# 1_routed_1register.net
KiCad netlist of a schematic drawn in EAGLE
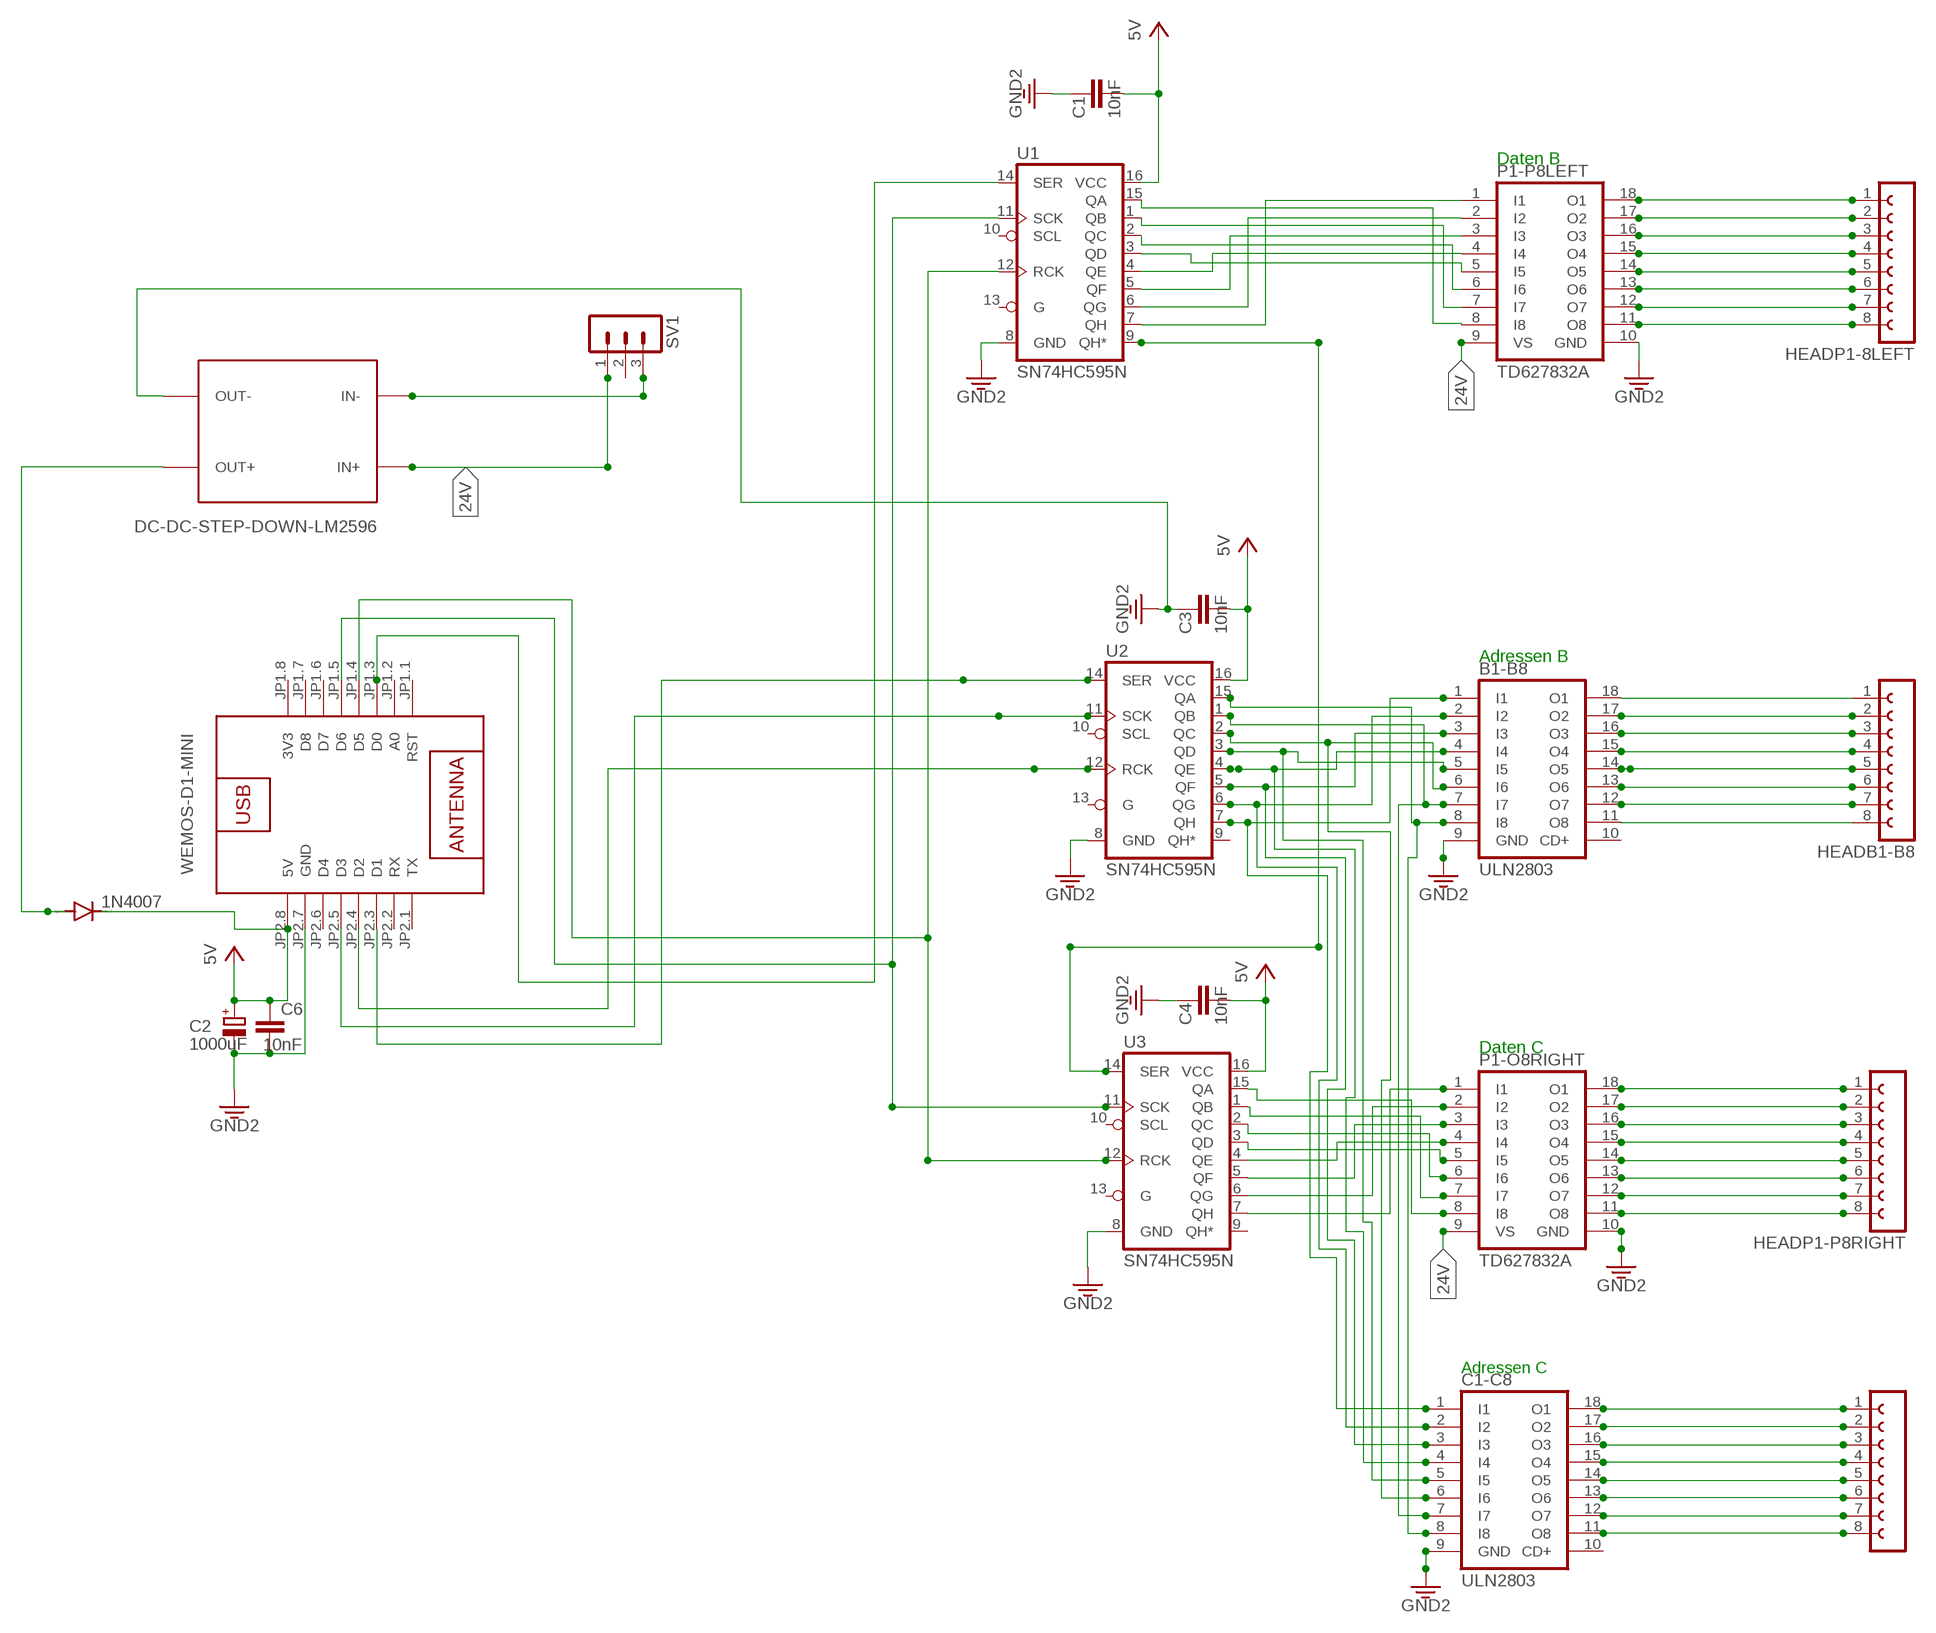
[diagram p0: schematic, sheet 1]

(export (version "E")
  (design (tool "Eeschema 10.0.6"))
  (components
    (comp (ref "1N4007")
      (value "DIODE-D-2.5")
      (footprint "eagle-import:D-2.5")
      (libsource (lib "eagle-import") (part "DIODE-D-2.5"))
    )
    (comp (ref "B1-B8")
      (value "ULN2803")
      (footprint "eagle-import:DIL18")
      (libsource (lib "eagle-import") (part "ULN2803A"))
    )
    (comp (ref "C1")
      (value "10nF")
      (footprint "eagle-import:C025-025X050")
      (libsource (lib "eagle-import") (part "C-EU025-025X050"))
    )
    (comp (ref "C1-C8")
      (value "ULN2803")
      (footprint "eagle-import:DIL18")
      (libsource (lib "eagle-import") (part "ULN2803A"))
    )
    (comp (ref "C2")
      (value "1000uF")
      (footprint "eagle-import:E5-10,5")
      (libsource (lib "eagle-import") (part "CPOL-EUE5-10.5"))
    )
    (comp (ref "C3")
      (value "10nF")
      (footprint "eagle-import:C025-025X050")
      (libsource (lib "eagle-import") (part "C-EU025-025X050"))
    )
    (comp (ref "C4")
      (value "10nF")
      (footprint "eagle-import:C025-025X050")
      (libsource (lib "eagle-import") (part "C-EU025-025X050"))
    )
    (comp (ref "C6")
      (value "10nF")
      (footprint "eagle-import:C025-025X050")
      (libsource (lib "eagle-import") (part "C-EU025-025X050"))
    )
    (comp (ref "HEADB1-B8")
      (value "FE08-1")
      (footprint "eagle-import:FE08")
      (libsource (lib "eagle-import") (part "FE08-1"))
    )
    (comp (ref "HEADC1-C8")
      (value "FE08-1")
      (footprint "eagle-import:FE08")
      (libsource (lib "eagle-import") (part "FE08-1"))
    )
    (comp (ref "HEADP1-8LEFT")
      (value "FE08-1")
      (footprint "eagle-import:FE08")
      (libsource (lib "eagle-import") (part "FE08-1"))
    )
    (comp (ref "HEADP1-P8RIGHT")
      (value "FE08-1")
      (footprint "eagle-import:FE08")
      (libsource (lib "eagle-import") (part "FE08-1"))
    )
    (comp (ref "P1-O8RIGHT")
      (value "TD627832A")
      (footprint "eagle-import:DIL18")
      (libsource (lib "eagle-import") (part "TD62783A2"))
    )
    (comp (ref "P1-P8LEFT")
      (value "TD627832A")
      (footprint "eagle-import:DIL18")
      (libsource (lib "eagle-import") (part "TD62783A2"))
    )
    (comp (ref "SV1")
      (value "MA03-1")
      (footprint "eagle-import:MA03-1")
      (libsource (lib "eagle-import") (part "MA03-1"))
    )
    (comp (ref "U$1")
      (value "WEMOS-D1-MINI")
      (footprint "eagle-import:WEMOS-D1-MINI")
      (libsource (lib "eagle-import") (part "WEMOS-D1-MINI"))
    )
    (comp (ref "U$2")
      (value "DC-DC-STEP-DOWN-LM2596")
      (footprint "eagle-import:DC-DC-STEP-DOWN-LM2596")
      (libsource (lib "eagle-import") (part "DC-DC-STEP-DOWN-LM2596"))
    )
    (comp (ref "U1")
      (value "SN74HC595N")
      (footprint "eagle-import:DIP16")
      (libsource (lib "eagle-import") (part "74595NHC"))
    )
    (comp (ref "U2")
      (value "SN74HC595N")
      (footprint "eagle-import:DIP16")
      (libsource (lib "eagle-import") (part "74595NHC"))
    )
    (comp (ref "U3")
      (value "SN74HC595N")
      (footprint "eagle-import:DIP16")
      (libsource (lib "eagle-import") (part "74595NHC"))
    )
  )
  (nets
    (net (code "1") (name "/3V3") (class "Default")
      (node (ref "U$1") (pin "JP1.8") (pinfunction "3V3_JP1.8") (pintype "power_in"))
    )
    (net (code "2") (name "5V") (class "Default")
      (node (ref "1N4007") (pin "C") (pinfunction "C_C") (pintype "passive"))
      (node (ref "C1") (pin "2") (pinfunction "2_2") (pintype "passive"))
      (node (ref "C2") (pin "+") (pinfunction "+_+") (pintype "passive"))
      (node (ref "C3") (pin "2") (pinfunction "2_2") (pintype "passive"))
      (node (ref "C4") (pin "2") (pinfunction "2_2") (pintype "passive"))
      (node (ref "C6") (pin "1") (pinfunction "1_1") (pintype "passive"))
      (node (ref "U$1") (pin "JP2.8") (pinfunction "5V_JP2.8") (pintype "power_in"))
      (node (ref "U1") (pin "16") (pinfunction "VCC_16") (pintype "power_in"))
      (node (ref "U2") (pin "16") (pinfunction "VCC_16") (pintype "power_in"))
      (node (ref "U3") (pin "16") (pinfunction "VCC_16") (pintype "power_in"))
    )
    (net (code "3") (name "24V") (class "Default")
      (node (ref "P1-O8RIGHT") (pin "9") (pinfunction "VS_9") (pintype "passive"))
      (node (ref "P1-P8LEFT") (pin "9") (pinfunction "VS_9") (pintype "passive"))
      (node (ref "SV1") (pin "1") (pinfunction "1_1") (pintype "passive"))
      (node (ref "U$2") (pin "IN+") (pinfunction "IN+_IN+") (pintype "bidirectional"))
    )
    (net (code "4") (name "GND2") (class "Default")
      (node (ref "B1-B8") (pin "9") (pinfunction "GND_9") (pintype "power_in"))
      (node (ref "C1") (pin "1") (pinfunction "1_1") (pintype "passive"))
      (node (ref "C1-C8") (pin "9") (pinfunction "GND_9") (pintype "power_in"))
      (node (ref "C2") (pin "-") (pinfunction "-_-") (pintype "passive"))
      (node (ref "C3") (pin "1") (pinfunction "1_1") (pintype "passive"))
      (node (ref "C4") (pin "1") (pinfunction "1_1") (pintype "passive"))
      (node (ref "C6") (pin "2") (pinfunction "2_2") (pintype "passive"))
      (node (ref "P1-O8RIGHT") (pin "10") (pinfunction "GND_10") (pintype "power_in"))
      (node (ref "P1-P8LEFT") (pin "10") (pinfunction "GND_10") (pintype "power_in"))
      (node (ref "U$1") (pin "JP2.7") (pinfunction "GND_JP2.7") (pintype "power_in"))
      (node (ref "U$2") (pin "OUT-") (pinfunction "OUT-_OUT-") (pintype "bidirectional"))
      (node (ref "U1") (pin "8") (pinfunction "GND_8") (pintype "power_in"))
      (node (ref "U2") (pin "8") (pinfunction "GND_8") (pintype "power_in"))
      (node (ref "U3") (pin "8") (pinfunction "GND_8") (pintype "power_in"))
    )
    (net (code "5") (name "Net-(1N4007-PadA)") (class "Default")
      (node (ref "1N4007") (pin "A") (pinfunction "A_A") (pintype "passive"))
      (node (ref "U$2") (pin "OUT+") (pinfunction "OUT+_OUT+") (pintype "bidirectional"))
    )
    (net (code "6") (name "Net-(B1-B8-I1)") (class "Default")
      (node (ref "B1-B8") (pin "1") (pinfunction "I1_1") (pintype "input"))
      (node (ref "C1-C8") (pin "1") (pinfunction "I1_1") (pintype "input"))
      (node (ref "U2") (pin "7") (pinfunction "QH_7") (pintype "tri_state"))
    )
    (net (code "7") (name "Net-(B1-B8-I2)") (class "Default")
      (node (ref "B1-B8") (pin "2") (pinfunction "I2_2") (pintype "input"))
      (node (ref "C1-C8") (pin "2") (pinfunction "I2_2") (pintype "input"))
      (node (ref "U2") (pin "6") (pinfunction "QG_6") (pintype "tri_state"))
    )
    (net (code "8") (name "Net-(B1-B8-I3)") (class "Default")
      (node (ref "B1-B8") (pin "3") (pinfunction "I3_3") (pintype "input"))
      (node (ref "C1-C8") (pin "3") (pinfunction "I3_3") (pintype "input"))
      (node (ref "U2") (pin "5") (pinfunction "QF_5") (pintype "tri_state"))
    )
    (net (code "9") (name "Net-(B1-B8-I4)") (class "Default")
      (node (ref "B1-B8") (pin "4") (pinfunction "I4_4") (pintype "input"))
      (node (ref "C1-C8") (pin "4") (pinfunction "I4_4") (pintype "input"))
      (node (ref "U2") (pin "4") (pinfunction "QE_4") (pintype "tri_state"))
    )
    (net (code "10") (name "Net-(B1-B8-I5)") (class "Default")
      (node (ref "B1-B8") (pin "5") (pinfunction "I5_5") (pintype "input"))
      (node (ref "C1-C8") (pin "5") (pinfunction "I5_5") (pintype "input"))
      (node (ref "U2") (pin "3") (pinfunction "QD_3") (pintype "tri_state"))
    )
    (net (code "11") (name "Net-(B1-B8-I6)") (class "Default")
      (node (ref "B1-B8") (pin "6") (pinfunction "I6_6") (pintype "input"))
      (node (ref "C1-C8") (pin "6") (pinfunction "I6_6") (pintype "input"))
      (node (ref "U2") (pin "2") (pinfunction "QC_2") (pintype "tri_state"))
    )
    (net (code "12") (name "Net-(B1-B8-I7)") (class "Default")
      (node (ref "B1-B8") (pin "7") (pinfunction "I7_7") (pintype "input"))
      (node (ref "C1-C8") (pin "7") (pinfunction "I7_7") (pintype "input"))
      (node (ref "U2") (pin "1") (pinfunction "QB_1") (pintype "tri_state"))
    )
    (net (code "13") (name "Net-(B1-B8-I8)") (class "Default")
      (node (ref "B1-B8") (pin "8") (pinfunction "I8_8") (pintype "input"))
      (node (ref "C1-C8") (pin "8") (pinfunction "I8_8") (pintype "input"))
      (node (ref "U2") (pin "15") (pinfunction "QA_15") (pintype "tri_state"))
    )
    (net (code "14") (name "Net-(B1-B8-O1)") (class "Default")
      (node (ref "B1-B8") (pin "18") (pinfunction "O1_18") (pintype "open_collector"))
      (node (ref "HEADB1-B8") (pin "1") (pinfunction "1_1") (pintype "passive"))
    )
    (net (code "15") (name "Net-(B1-B8-O2)") (class "Default")
      (node (ref "B1-B8") (pin "17") (pinfunction "O2_17") (pintype "open_collector"))
      (node (ref "HEADB1-B8") (pin "2") (pinfunction "2_2") (pintype "passive"))
    )
    (net (code "16") (name "Net-(B1-B8-O3)") (class "Default")
      (node (ref "B1-B8") (pin "16") (pinfunction "O3_16") (pintype "open_collector"))
      (node (ref "HEADB1-B8") (pin "3") (pinfunction "3_3") (pintype "passive"))
    )
    (net (code "17") (name "Net-(B1-B8-O4)") (class "Default")
      (node (ref "B1-B8") (pin "15") (pinfunction "O4_15") (pintype "open_collector"))
      (node (ref "HEADB1-B8") (pin "4") (pinfunction "4_4") (pintype "passive"))
    )
    (net (code "18") (name "Net-(B1-B8-O5)") (class "Default")
      (node (ref "B1-B8") (pin "14") (pinfunction "O5_14") (pintype "open_collector"))
      (node (ref "HEADB1-B8") (pin "5") (pinfunction "5_5") (pintype "passive"))
    )
    (net (code "19") (name "Net-(B1-B8-O6)") (class "Default")
      (node (ref "B1-B8") (pin "13") (pinfunction "O6_13") (pintype "open_collector"))
      (node (ref "HEADB1-B8") (pin "6") (pinfunction "6_6") (pintype "passive"))
    )
    (net (code "20") (name "Net-(B1-B8-O7)") (class "Default")
      (node (ref "B1-B8") (pin "12") (pinfunction "O7_12") (pintype "open_collector"))
      (node (ref "HEADB1-B8") (pin "7") (pinfunction "7_7") (pintype "passive"))
    )
    (net (code "21") (name "Net-(B1-B8-O8)") (class "Default")
      (node (ref "B1-B8") (pin "11") (pinfunction "O8_11") (pintype "open_collector"))
      (node (ref "HEADB1-B8") (pin "8") (pinfunction "8_8") (pintype "passive"))
    )
    (net (code "22") (name "Net-(C1-C8-O1)") (class "Default")
      (node (ref "C1-C8") (pin "18") (pinfunction "O1_18") (pintype "open_collector"))
      (node (ref "HEADC1-C8") (pin "1") (pinfunction "1_1") (pintype "passive"))
    )
    (net (code "23") (name "Net-(C1-C8-O2)") (class "Default")
      (node (ref "C1-C8") (pin "17") (pinfunction "O2_17") (pintype "open_collector"))
      (node (ref "HEADC1-C8") (pin "2") (pinfunction "2_2") (pintype "passive"))
    )
    (net (code "24") (name "Net-(C1-C8-O3)") (class "Default")
      (node (ref "C1-C8") (pin "16") (pinfunction "O3_16") (pintype "open_collector"))
      (node (ref "HEADC1-C8") (pin "3") (pinfunction "3_3") (pintype "passive"))
    )
    (net (code "25") (name "Net-(C1-C8-O4)") (class "Default")
      (node (ref "C1-C8") (pin "15") (pinfunction "O4_15") (pintype "open_collector"))
      (node (ref "HEADC1-C8") (pin "4") (pinfunction "4_4") (pintype "passive"))
    )
    (net (code "26") (name "Net-(C1-C8-O5)") (class "Default")
      (node (ref "C1-C8") (pin "14") (pinfunction "O5_14") (pintype "open_collector"))
      (node (ref "HEADC1-C8") (pin "5") (pinfunction "5_5") (pintype "passive"))
    )
    (net (code "27") (name "Net-(C1-C8-O6)") (class "Default")
      (node (ref "C1-C8") (pin "13") (pinfunction "O6_13") (pintype "open_collector"))
      (node (ref "HEADC1-C8") (pin "6") (pinfunction "6_6") (pintype "passive"))
    )
    (net (code "28") (name "Net-(C1-C8-O7)") (class "Default")
      (node (ref "C1-C8") (pin "12") (pinfunction "O7_12") (pintype "open_collector"))
      (node (ref "HEADC1-C8") (pin "7") (pinfunction "7_7") (pintype "passive"))
    )
    (net (code "29") (name "Net-(C1-C8-O8)") (class "Default")
      (node (ref "C1-C8") (pin "11") (pinfunction "O8_11") (pintype "open_collector"))
      (node (ref "HEADC1-C8") (pin "8") (pinfunction "8_8") (pintype "passive"))
    )
    (net (code "30") (name "Net-(P1-O8RIGHT-I1)") (class "Default")
      (node (ref "P1-O8RIGHT") (pin "1") (pinfunction "I1_1") (pintype "input"))
      (node (ref "U3") (pin "7") (pinfunction "QH_7") (pintype "tri_state"))
    )
    (net (code "31") (name "Net-(P1-O8RIGHT-I2)") (class "Default")
      (node (ref "P1-O8RIGHT") (pin "2") (pinfunction "I2_2") (pintype "input"))
      (node (ref "U3") (pin "6") (pinfunction "QG_6") (pintype "tri_state"))
    )
    (net (code "32") (name "Net-(P1-O8RIGHT-I3)") (class "Default")
      (node (ref "P1-O8RIGHT") (pin "3") (pinfunction "I3_3") (pintype "input"))
      (node (ref "U3") (pin "5") (pinfunction "QF_5") (pintype "tri_state"))
    )
    (net (code "33") (name "Net-(P1-O8RIGHT-I4)") (class "Default")
      (node (ref "P1-O8RIGHT") (pin "4") (pinfunction "I4_4") (pintype "input"))
      (node (ref "U3") (pin "4") (pinfunction "QE_4") (pintype "tri_state"))
    )
    (net (code "34") (name "Net-(P1-O8RIGHT-I5)") (class "Default")
      (node (ref "P1-O8RIGHT") (pin "5") (pinfunction "I5_5") (pintype "input"))
      (node (ref "U3") (pin "3") (pinfunction "QD_3") (pintype "tri_state"))
    )
    (net (code "35") (name "Net-(P1-O8RIGHT-I6)") (class "Default")
      (node (ref "P1-O8RIGHT") (pin "6") (pinfunction "I6_6") (pintype "input"))
      (node (ref "U3") (pin "2") (pinfunction "QC_2") (pintype "tri_state"))
    )
    (net (code "36") (name "Net-(P1-O8RIGHT-I7)") (class "Default")
      (node (ref "P1-O8RIGHT") (pin "7") (pinfunction "I7_7") (pintype "input"))
      (node (ref "U3") (pin "1") (pinfunction "QB_1") (pintype "tri_state"))
    )
    (net (code "37") (name "Net-(P1-O8RIGHT-I8)") (class "Default")
      (node (ref "P1-O8RIGHT") (pin "8") (pinfunction "I8_8") (pintype "input"))
      (node (ref "U3") (pin "15") (pinfunction "QA_15") (pintype "tri_state"))
    )
    (net (code "38") (name "Net-(P1-O8RIGHT-O1)") (class "Default")
      (node (ref "HEADP1-P8RIGHT") (pin "1") (pinfunction "1_1") (pintype "passive"))
      (node (ref "P1-O8RIGHT") (pin "18") (pinfunction "O1_18") (pintype "open_collector"))
    )
    (net (code "39") (name "Net-(P1-O8RIGHT-O2)") (class "Default")
      (node (ref "HEADP1-P8RIGHT") (pin "2") (pinfunction "2_2") (pintype "passive"))
      (node (ref "P1-O8RIGHT") (pin "17") (pinfunction "O2_17") (pintype "open_collector"))
    )
    (net (code "40") (name "Net-(P1-O8RIGHT-O3)") (class "Default")
      (node (ref "HEADP1-P8RIGHT") (pin "3") (pinfunction "3_3") (pintype "passive"))
      (node (ref "P1-O8RIGHT") (pin "16") (pinfunction "O3_16") (pintype "open_collector"))
    )
    (net (code "41") (name "Net-(P1-O8RIGHT-O4)") (class "Default")
      (node (ref "HEADP1-P8RIGHT") (pin "4") (pinfunction "4_4") (pintype "passive"))
      (node (ref "P1-O8RIGHT") (pin "15") (pinfunction "O4_15") (pintype "open_collector"))
    )
    (net (code "42") (name "Net-(P1-O8RIGHT-O5)") (class "Default")
      (node (ref "HEADP1-P8RIGHT") (pin "5") (pinfunction "5_5") (pintype "passive"))
      (node (ref "P1-O8RIGHT") (pin "14") (pinfunction "O5_14") (pintype "open_collector"))
    )
    (net (code "43") (name "Net-(P1-O8RIGHT-O6)") (class "Default")
      (node (ref "HEADP1-P8RIGHT") (pin "6") (pinfunction "6_6") (pintype "passive"))
      (node (ref "P1-O8RIGHT") (pin "13") (pinfunction "O6_13") (pintype "open_collector"))
    )
    (net (code "44") (name "Net-(P1-O8RIGHT-O7)") (class "Default")
      (node (ref "HEADP1-P8RIGHT") (pin "7") (pinfunction "7_7") (pintype "passive"))
      (node (ref "P1-O8RIGHT") (pin "12") (pinfunction "O7_12") (pintype "open_collector"))
    )
    (net (code "45") (name "Net-(P1-O8RIGHT-O8)") (class "Default")
      (node (ref "HEADP1-P8RIGHT") (pin "8") (pinfunction "8_8") (pintype "passive"))
      (node (ref "P1-O8RIGHT") (pin "11") (pinfunction "O8_11") (pintype "open_collector"))
    )
    (net (code "46") (name "Net-(P1-P8LEFT-I1)") (class "Default")
      (node (ref "P1-P8LEFT") (pin "1") (pinfunction "I1_1") (pintype "input"))
      (node (ref "U1") (pin "7") (pinfunction "QH_7") (pintype "tri_state"))
    )
    (net (code "47") (name "Net-(P1-P8LEFT-I2)") (class "Default")
      (node (ref "P1-P8LEFT") (pin "2") (pinfunction "I2_2") (pintype "input"))
      (node (ref "U1") (pin "6") (pinfunction "QG_6") (pintype "tri_state"))
    )
    (net (code "48") (name "Net-(P1-P8LEFT-I3)") (class "Default")
      (node (ref "P1-P8LEFT") (pin "3") (pinfunction "I3_3") (pintype "input"))
      (node (ref "U1") (pin "5") (pinfunction "QF_5") (pintype "tri_state"))
    )
    (net (code "49") (name "Net-(P1-P8LEFT-I4)") (class "Default")
      (node (ref "P1-P8LEFT") (pin "4") (pinfunction "I4_4") (pintype "input"))
      (node (ref "U1") (pin "4") (pinfunction "QE_4") (pintype "tri_state"))
    )
    (net (code "50") (name "Net-(P1-P8LEFT-I5)") (class "Default")
      (node (ref "P1-P8LEFT") (pin "5") (pinfunction "I5_5") (pintype "input"))
      (node (ref "U1") (pin "3") (pinfunction "QD_3") (pintype "tri_state"))
    )
    (net (code "51") (name "Net-(P1-P8LEFT-I6)") (class "Default")
      (node (ref "P1-P8LEFT") (pin "6") (pinfunction "I6_6") (pintype "input"))
      (node (ref "U1") (pin "2") (pinfunction "QC_2") (pintype "tri_state"))
    )
    (net (code "52") (name "Net-(P1-P8LEFT-I7)") (class "Default")
      (node (ref "P1-P8LEFT") (pin "7") (pinfunction "I7_7") (pintype "input"))
      (node (ref "U1") (pin "1") (pinfunction "QB_1") (pintype "tri_state"))
    )
    (net (code "53") (name "Net-(P1-P8LEFT-I8)") (class "Default")
      (node (ref "P1-P8LEFT") (pin "8") (pinfunction "I8_8") (pintype "input"))
      (node (ref "U1") (pin "15") (pinfunction "QA_15") (pintype "tri_state"))
    )
    (net (code "54") (name "Net-(P1-P8LEFT-O1)") (class "Default")
      (node (ref "HEADP1-8LEFT") (pin "1") (pinfunction "1_1") (pintype "passive"))
      (node (ref "P1-P8LEFT") (pin "18") (pinfunction "O1_18") (pintype "open_collector"))
    )
    (net (code "55") (name "Net-(P1-P8LEFT-O2)") (class "Default")
      (node (ref "HEADP1-8LEFT") (pin "2") (pinfunction "2_2") (pintype "passive"))
      (node (ref "P1-P8LEFT") (pin "17") (pinfunction "O2_17") (pintype "open_collector"))
    )
    (net (code "56") (name "Net-(P1-P8LEFT-O3)") (class "Default")
      (node (ref "HEADP1-8LEFT") (pin "3") (pinfunction "3_3") (pintype "passive"))
      (node (ref "P1-P8LEFT") (pin "16") (pinfunction "O3_16") (pintype "open_collector"))
    )
    (net (code "57") (name "Net-(P1-P8LEFT-O4)") (class "Default")
      (node (ref "HEADP1-8LEFT") (pin "4") (pinfunction "4_4") (pintype "passive"))
      (node (ref "P1-P8LEFT") (pin "15") (pinfunction "O4_15") (pintype "open_collector"))
    )
    (net (code "58") (name "Net-(P1-P8LEFT-O5)") (class "Default")
      (node (ref "HEADP1-8LEFT") (pin "5") (pinfunction "5_5") (pintype "passive"))
      (node (ref "P1-P8LEFT") (pin "14") (pinfunction "O5_14") (pintype "open_collector"))
    )
    (net (code "59") (name "Net-(P1-P8LEFT-O6)") (class "Default")
      (node (ref "HEADP1-8LEFT") (pin "6") (pinfunction "6_6") (pintype "passive"))
      (node (ref "P1-P8LEFT") (pin "13") (pinfunction "O6_13") (pintype "open_collector"))
    )
    (net (code "60") (name "Net-(P1-P8LEFT-O7)") (class "Default")
      (node (ref "HEADP1-8LEFT") (pin "7") (pinfunction "7_7") (pintype "passive"))
      (node (ref "P1-P8LEFT") (pin "12") (pinfunction "O7_12") (pintype "open_collector"))
    )
    (net (code "61") (name "Net-(P1-P8LEFT-O8)") (class "Default")
      (node (ref "HEADP1-8LEFT") (pin "8") (pinfunction "8_8") (pintype "passive"))
      (node (ref "P1-P8LEFT") (pin "11") (pinfunction "O8_11") (pintype "open_collector"))
    )
    (net (code "62") (name "Net-(SV1-Pad3)") (class "Default")
      (node (ref "SV1") (pin "3") (pinfunction "3_3") (pintype "passive"))
      (node (ref "U$2") (pin "IN-") (pinfunction "IN-_IN-") (pintype "bidirectional"))
    )
    (net (code "63") (name "Net-(U$1-D0)") (class "Default")
      (node (ref "U$1") (pin "JP1.3") (pinfunction "D0_JP1.3") (pintype "bidirectional"))
      (node (ref "U1") (pin "14") (pinfunction "SER_14") (pintype "input"))
    )
    (net (code "64") (name "Net-(U$1-D1)") (class "Default")
      (node (ref "U$1") (pin "JP2.3") (pinfunction "D1_JP2.3") (pintype "bidirectional"))
      (node (ref "U2") (pin "14") (pinfunction "SER_14") (pintype "input"))
    )
    (net (code "65") (name "Net-(U$1-D2)") (class "Default")
      (node (ref "U$1") (pin "JP2.4") (pinfunction "D2_JP2.4") (pintype "bidirectional"))
      (node (ref "U2") (pin "12") (pinfunction "RCK_12") (pintype "input"))
    )
    (net (code "66") (name "Net-(U$1-D3)") (class "Default")
      (node (ref "U$1") (pin "JP2.5") (pinfunction "D3_JP2.5") (pintype "bidirectional"))
      (node (ref "U2") (pin "11") (pinfunction "SCK_11") (pintype "input"))
    )
    (net (code "67") (name "Net-(U$1-D5)") (class "Default")
      (node (ref "U$1") (pin "JP1.4") (pinfunction "D5_JP1.4") (pintype "bidirectional"))
      (node (ref "U1") (pin "12") (pinfunction "RCK_12") (pintype "input"))
      (node (ref "U3") (pin "12") (pinfunction "RCK_12") (pintype "input"))
    )
    (net (code "68") (name "Net-(U$1-D6)") (class "Default")
      (node (ref "U$1") (pin "JP1.5") (pinfunction "D6_JP1.5") (pintype "bidirectional"))
      (node (ref "U1") (pin "11") (pinfunction "SCK_11") (pintype "input"))
      (node (ref "U3") (pin "11") (pinfunction "SCK_11") (pintype "input"))
    )
    (net (code "69") (name "Net-(U1-QH*)") (class "Default")
      (node (ref "U1") (pin "9") (pinfunction "QH*_9") (pintype "tri_state"))
      (node (ref "U3") (pin "14") (pinfunction "SER_14") (pintype "input"))
    )
    (net (code "70") (name "unconnected-(B1-B8-CD+-Pad10)") (class "Default")
      (node (ref "B1-B8") (pin "10") (pinfunction "CD+_10") (pintype "passive"))
    )
    (net (code "71") (name "unconnected-(C1-C8-CD+-Pad10)") (class "Default")
      (node (ref "C1-C8") (pin "10") (pinfunction "CD+_10") (pintype "passive"))
    )
    (net (code "72") (name "unconnected-(SV1-Pad2)") (class "Default")
      (node (ref "SV1") (pin "2") (pinfunction "2_2") (pintype "passive"))
    )
    (net (code "73") (name "unconnected-(U$1-A0-PadJP1.2)") (class "Default")
      (node (ref "U$1") (pin "JP1.2") (pinfunction "A0_JP1.2") (pintype "bidirectional"))
    )
    (net (code "74") (name "unconnected-(U$1-D4-PadJP2.6)") (class "Default")
      (node (ref "U$1") (pin "JP2.6") (pinfunction "D4_JP2.6") (pintype "bidirectional"))
    )
    (net (code "75") (name "unconnected-(U$1-D7-PadJP1.6)") (class "Default")
      (node (ref "U$1") (pin "JP1.6") (pinfunction "D7_JP1.6") (pintype "bidirectional"))
    )
    (net (code "76") (name "unconnected-(U$1-D8-PadJP1.7)") (class "Default")
      (node (ref "U$1") (pin "JP1.7") (pinfunction "D8_JP1.7") (pintype "bidirectional"))
    )
    (net (code "77") (name "unconnected-(U$1-RST-PadJP1.1)") (class "Default")
      (node (ref "U$1") (pin "JP1.1") (pinfunction "RST_JP1.1") (pintype "bidirectional"))
    )
    (net (code "78") (name "unconnected-(U$1-RX-PadJP2.2)") (class "Default")
      (node (ref "U$1") (pin "JP2.2") (pinfunction "RX_JP2.2") (pintype "bidirectional"))
    )
    (net (code "79") (name "unconnected-(U$1-TX-PadJP2.1)") (class "Default")
      (node (ref "U$1") (pin "JP2.1") (pinfunction "TX_JP2.1") (pintype "bidirectional"))
    )
    (net (code "80") (name "unconnected-(U1-G-Pad13)") (class "Default")
      (node (ref "U1") (pin "13") (pinfunction "G_13") (pintype "input"))
    )
    (net (code "81") (name "unconnected-(U1-SCL-Pad10)") (class "Default")
      (node (ref "U1") (pin "10") (pinfunction "SCL_10") (pintype "input"))
    )
    (net (code "82") (name "unconnected-(U2-G-Pad13)") (class "Default")
      (node (ref "U2") (pin "13") (pinfunction "G_13") (pintype "input"))
    )
    (net (code "83") (name "unconnected-(U2-QH*-Pad9)") (class "Default")
      (node (ref "U2") (pin "9") (pinfunction "QH*_9") (pintype "tri_state"))
    )
    (net (code "84") (name "unconnected-(U2-SCL-Pad10)") (class "Default")
      (node (ref "U2") (pin "10") (pinfunction "SCL_10") (pintype "input"))
    )
    (net (code "85") (name "unconnected-(U3-G-Pad13)") (class "Default")
      (node (ref "U3") (pin "13") (pinfunction "G_13") (pintype "input"))
    )
    (net (code "86") (name "unconnected-(U3-QH*-Pad9)") (class "Default")
      (node (ref "U3") (pin "9") (pinfunction "QH*_9") (pintype "tri_state"))
    )
    (net (code "87") (name "unconnected-(U3-SCL-Pad10)") (class "Default")
      (node (ref "U3") (pin "10") (pinfunction "SCL_10") (pintype "input"))
    )
  )
)
